# cubesat_board_connector.net
KiCad netlist of a schematic drawn in Altium Designer
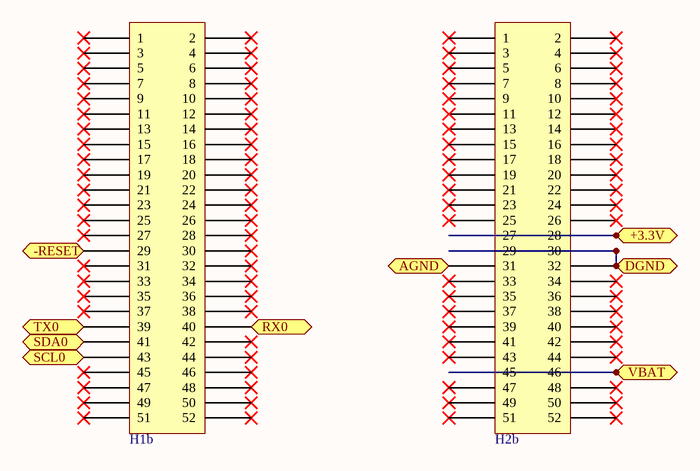
[diagram p0: cubesat board connector.SchDoc]

(export (version "E")
  (design (tool "Eeschema 10.0.6"))
  (components
    (comp (ref "H1b") (value "CSC Header") (libsource (lib "allspace_schem") (part "CubeSat Connector")))
    (comp (ref "H2b") (value "CSC Header") (libsource (lib "allspace_schem") (part "CubeSat Connector")))
  )
  (nets
    (net (code "1") (name "/+3.3V") (class "Default")
      (node (ref "H2b") (pin "27") (pinfunction "27_27") (pintype "passive"))
      (node (ref "H2b") (pin "28") (pinfunction "28_28") (pintype "passive"))
    )
    (net (code "2") (name "/-RESET") (class "Default")
      (node (ref "H1b") (pin "29") (pinfunction "29_29") (pintype "passive"))
    )
    (net (code "3") (name "/AGND") (class "Default")
      (node (ref "H2b") (pin "31") (pinfunction "31_31") (pintype "passive"))
    )
    (net (code "4") (name "/DGND") (class "Default")
      (node (ref "H2b") (pin "29") (pinfunction "29_29") (pintype "passive"))
      (node (ref "H2b") (pin "30") (pinfunction "30_30") (pintype "passive"))
      (node (ref "H2b") (pin "32") (pinfunction "32_32") (pintype "passive"))
    )
    (net (code "5") (name "/RX0") (class "Default")
      (node (ref "H1b") (pin "40") (pinfunction "40_40") (pintype "passive"))
    )
    (net (code "6") (name "/SCL0") (class "Default")
      (node (ref "H1b") (pin "43") (pinfunction "43_43") (pintype "passive"))
    )
    (net (code "7") (name "/SDA0") (class "Default")
      (node (ref "H1b") (pin "41") (pinfunction "41_41") (pintype "passive"))
    )
    (net (code "8") (name "/TX0") (class "Default")
      (node (ref "H1b") (pin "39") (pinfunction "39_39") (pintype "passive"))
    )
    (net (code "9") (name "/VBAT") (class "Default")
      (node (ref "H2b") (pin "45") (pinfunction "45_45") (pintype "passive"))
      (node (ref "H2b") (pin "46") (pinfunction "46_46") (pintype "passive"))
    )
    (net (code "10") (name "unconnected-(H1b-Pad1)") (class "Default")
      (node (ref "H1b") (pin "1") (pinfunction "1_1") (pintype "passive+no_connect"))
    )
    (net (code "11") (name "unconnected-(H1b-Pad2)") (class "Default")
      (node (ref "H1b") (pin "2") (pinfunction "2_2") (pintype "passive+no_connect"))
    )
    (net (code "12") (name "unconnected-(H1b-Pad3)") (class "Default")
      (node (ref "H1b") (pin "3") (pinfunction "3_3") (pintype "passive+no_connect"))
    )
    (net (code "13") (name "unconnected-(H1b-Pad4)") (class "Default")
      (node (ref "H1b") (pin "4") (pinfunction "4_4") (pintype "passive+no_connect"))
    )
    (net (code "14") (name "unconnected-(H1b-Pad5)") (class "Default")
      (node (ref "H1b") (pin "5") (pinfunction "5_5") (pintype "passive+no_connect"))
    )
    (net (code "15") (name "unconnected-(H1b-Pad6)") (class "Default")
      (node (ref "H1b") (pin "6") (pinfunction "6_6") (pintype "passive+no_connect"))
    )
    (net (code "16") (name "unconnected-(H1b-Pad7)") (class "Default")
      (node (ref "H1b") (pin "7") (pinfunction "7_7") (pintype "passive+no_connect"))
    )
    (net (code "17") (name "unconnected-(H1b-Pad8)") (class "Default")
      (node (ref "H1b") (pin "8") (pinfunction "8_8") (pintype "passive+no_connect"))
    )
    (net (code "18") (name "unconnected-(H1b-Pad9)") (class "Default")
      (node (ref "H1b") (pin "9") (pinfunction "9_9") (pintype "passive+no_connect"))
    )
    (net (code "19") (name "unconnected-(H1b-Pad10)") (class "Default")
      (node (ref "H1b") (pin "10") (pinfunction "10_10") (pintype "passive+no_connect"))
    )
    (net (code "20") (name "unconnected-(H1b-Pad11)") (class "Default")
      (node (ref "H1b") (pin "11") (pinfunction "11_11") (pintype "passive+no_connect"))
    )
    (net (code "21") (name "unconnected-(H1b-Pad12)") (class "Default")
      (node (ref "H1b") (pin "12") (pinfunction "12_12") (pintype "passive+no_connect"))
    )
    (net (code "22") (name "unconnected-(H1b-Pad13)") (class "Default")
      (node (ref "H1b") (pin "13") (pinfunction "13_13") (pintype "passive+no_connect"))
    )
    (net (code "23") (name "unconnected-(H1b-Pad14)") (class "Default")
      (node (ref "H1b") (pin "14") (pinfunction "14_14") (pintype "passive+no_connect"))
    )
    (net (code "24") (name "unconnected-(H1b-Pad15)") (class "Default")
      (node (ref "H1b") (pin "15") (pinfunction "15_15") (pintype "passive+no_connect"))
    )
    (net (code "25") (name "unconnected-(H1b-Pad16)") (class "Default")
      (node (ref "H1b") (pin "16") (pinfunction "16_16") (pintype "passive+no_connect"))
    )
    (net (code "26") (name "unconnected-(H1b-Pad17)") (class "Default")
      (node (ref "H1b") (pin "17") (pinfunction "17_17") (pintype "passive+no_connect"))
    )
    (net (code "27") (name "unconnected-(H1b-Pad18)") (class "Default")
      (node (ref "H1b") (pin "18") (pinfunction "18_18") (pintype "passive+no_connect"))
    )
    (net (code "28") (name "unconnected-(H1b-Pad19)") (class "Default")
      (node (ref "H1b") (pin "19") (pinfunction "19_19") (pintype "passive+no_connect"))
    )
    (net (code "29") (name "unconnected-(H1b-Pad20)") (class "Default")
      (node (ref "H1b") (pin "20") (pinfunction "20_20") (pintype "passive+no_connect"))
    )
    (net (code "30") (name "unconnected-(H1b-Pad21)") (class "Default")
      (node (ref "H1b") (pin "21") (pinfunction "21_21") (pintype "passive+no_connect"))
    )
    (net (code "31") (name "unconnected-(H1b-Pad22)") (class "Default")
      (node (ref "H1b") (pin "22") (pinfunction "22_22") (pintype "passive+no_connect"))
    )
    (net (code "32") (name "unconnected-(H1b-Pad23)") (class "Default")
      (node (ref "H1b") (pin "23") (pinfunction "23_23") (pintype "passive+no_connect"))
    )
    (net (code "33") (name "unconnected-(H1b-Pad24)") (class "Default")
      (node (ref "H1b") (pin "24") (pinfunction "24_24") (pintype "passive+no_connect"))
    )
    (net (code "34") (name "unconnected-(H1b-Pad25)") (class "Default")
      (node (ref "H1b") (pin "25") (pinfunction "25_25") (pintype "passive+no_connect"))
    )
    (net (code "35") (name "unconnected-(H1b-Pad26)") (class "Default")
      (node (ref "H1b") (pin "26") (pinfunction "26_26") (pintype "passive+no_connect"))
    )
    (net (code "36") (name "unconnected-(H1b-Pad27)") (class "Default")
      (node (ref "H1b") (pin "27") (pinfunction "27_27") (pintype "passive+no_connect"))
    )
    (net (code "37") (name "unconnected-(H1b-Pad28)") (class "Default")
      (node (ref "H1b") (pin "28") (pinfunction "28_28") (pintype "passive+no_connect"))
    )
    (net (code "38") (name "unconnected-(H1b-Pad30)") (class "Default")
      (node (ref "H1b") (pin "30") (pinfunction "30_30") (pintype "passive+no_connect"))
    )
    (net (code "39") (name "unconnected-(H1b-Pad31)") (class "Default")
      (node (ref "H1b") (pin "31") (pinfunction "31_31") (pintype "passive+no_connect"))
    )
    (net (code "40") (name "unconnected-(H1b-Pad32)") (class "Default")
      (node (ref "H1b") (pin "32") (pinfunction "32_32") (pintype "passive+no_connect"))
    )
    (net (code "41") (name "unconnected-(H1b-Pad33)") (class "Default")
      (node (ref "H1b") (pin "33") (pinfunction "33_33") (pintype "passive+no_connect"))
    )
    (net (code "42") (name "unconnected-(H1b-Pad34)") (class "Default")
      (node (ref "H1b") (pin "34") (pinfunction "34_34") (pintype "passive+no_connect"))
    )
    (net (code "43") (name "unconnected-(H1b-Pad35)") (class "Default")
      (node (ref "H1b") (pin "35") (pinfunction "35_35") (pintype "passive+no_connect"))
    )
    (net (code "44") (name "unconnected-(H1b-Pad36)") (class "Default")
      (node (ref "H1b") (pin "36") (pinfunction "36_36") (pintype "passive+no_connect"))
    )
    (net (code "45") (name "unconnected-(H1b-Pad37)") (class "Default")
      (node (ref "H1b") (pin "37") (pinfunction "37_37") (pintype "passive+no_connect"))
    )
    (net (code "46") (name "unconnected-(H1b-Pad38)") (class "Default")
      (node (ref "H1b") (pin "38") (pinfunction "38_38") (pintype "passive+no_connect"))
    )
    (net (code "47") (name "unconnected-(H1b-Pad42)") (class "Default")
      (node (ref "H1b") (pin "42") (pinfunction "42_42") (pintype "passive+no_connect"))
    )
    (net (code "48") (name "unconnected-(H1b-Pad44)") (class "Default")
      (node (ref "H1b") (pin "44") (pinfunction "44_44") (pintype "passive+no_connect"))
    )
    (net (code "49") (name "unconnected-(H1b-Pad45)") (class "Default")
      (node (ref "H1b") (pin "45") (pinfunction "45_45") (pintype "passive+no_connect"))
    )
    (net (code "50") (name "unconnected-(H1b-Pad46)") (class "Default")
      (node (ref "H1b") (pin "46") (pinfunction "46_46") (pintype "passive+no_connect"))
    )
    (net (code "51") (name "unconnected-(H1b-Pad47)") (class "Default")
      (node (ref "H1b") (pin "47") (pinfunction "47_47") (pintype "passive+no_connect"))
    )
    (net (code "52") (name "unconnected-(H1b-Pad48)") (class "Default")
      (node (ref "H1b") (pin "48") (pinfunction "48_48") (pintype "passive+no_connect"))
    )
    (net (code "53") (name "unconnected-(H1b-Pad49)") (class "Default")
      (node (ref "H1b") (pin "49") (pinfunction "49_49") (pintype "passive+no_connect"))
    )
    (net (code "54") (name "unconnected-(H1b-Pad50)") (class "Default")
      (node (ref "H1b") (pin "50") (pinfunction "50_50") (pintype "passive+no_connect"))
    )
    (net (code "55") (name "unconnected-(H1b-Pad51)") (class "Default")
      (node (ref "H1b") (pin "51") (pinfunction "51_51") (pintype "passive+no_connect"))
    )
    (net (code "56") (name "unconnected-(H1b-Pad52)") (class "Default")
      (node (ref "H1b") (pin "52") (pinfunction "52_52") (pintype "passive+no_connect"))
    )
    (net (code "57") (name "unconnected-(H2b-Pad1)") (class "Default")
      (node (ref "H2b") (pin "1") (pinfunction "1_1") (pintype "passive+no_connect"))
    )
    (net (code "58") (name "unconnected-(H2b-Pad2)") (class "Default")
      (node (ref "H2b") (pin "2") (pinfunction "2_2") (pintype "passive+no_connect"))
    )
    (net (code "59") (name "unconnected-(H2b-Pad3)") (class "Default")
      (node (ref "H2b") (pin "3") (pinfunction "3_3") (pintype "passive+no_connect"))
    )
    (net (code "60") (name "unconnected-(H2b-Pad4)") (class "Default")
      (node (ref "H2b") (pin "4") (pinfunction "4_4") (pintype "passive+no_connect"))
    )
    (net (code "61") (name "unconnected-(H2b-Pad5)") (class "Default")
      (node (ref "H2b") (pin "5") (pinfunction "5_5") (pintype "passive+no_connect"))
    )
    (net (code "62") (name "unconnected-(H2b-Pad6)") (class "Default")
      (node (ref "H2b") (pin "6") (pinfunction "6_6") (pintype "passive+no_connect"))
    )
    (net (code "63") (name "unconnected-(H2b-Pad7)") (class "Default")
      (node (ref "H2b") (pin "7") (pinfunction "7_7") (pintype "passive+no_connect"))
    )
    (net (code "64") (name "unconnected-(H2b-Pad8)") (class "Default")
      (node (ref "H2b") (pin "8") (pinfunction "8_8") (pintype "passive+no_connect"))
    )
    (net (code "65") (name "unconnected-(H2b-Pad9)") (class "Default")
      (node (ref "H2b") (pin "9") (pinfunction "9_9") (pintype "passive+no_connect"))
    )
    (net (code "66") (name "unconnected-(H2b-Pad10)") (class "Default")
      (node (ref "H2b") (pin "10") (pinfunction "10_10") (pintype "passive+no_connect"))
    )
    (net (code "67") (name "unconnected-(H2b-Pad11)") (class "Default")
      (node (ref "H2b") (pin "11") (pinfunction "11_11") (pintype "passive+no_connect"))
    )
    (net (code "68") (name "unconnected-(H2b-Pad12)") (class "Default")
      (node (ref "H2b") (pin "12") (pinfunction "12_12") (pintype "passive+no_connect"))
    )
    (net (code "69") (name "unconnected-(H2b-Pad13)") (class "Default")
      (node (ref "H2b") (pin "13") (pinfunction "13_13") (pintype "passive+no_connect"))
    )
    (net (code "70") (name "unconnected-(H2b-Pad14)") (class "Default")
      (node (ref "H2b") (pin "14") (pinfunction "14_14") (pintype "passive+no_connect"))
    )
    (net (code "71") (name "unconnected-(H2b-Pad15)") (class "Default")
      (node (ref "H2b") (pin "15") (pinfunction "15_15") (pintype "passive+no_connect"))
    )
    (net (code "72") (name "unconnected-(H2b-Pad16)") (class "Default")
      (node (ref "H2b") (pin "16") (pinfunction "16_16") (pintype "passive+no_connect"))
    )
    (net (code "73") (name "unconnected-(H2b-Pad17)") (class "Default")
      (node (ref "H2b") (pin "17") (pinfunction "17_17") (pintype "passive+no_connect"))
    )
    (net (code "74") (name "unconnected-(H2b-Pad18)") (class "Default")
      (node (ref "H2b") (pin "18") (pinfunction "18_18") (pintype "passive+no_connect"))
    )
    (net (code "75") (name "unconnected-(H2b-Pad19)") (class "Default")
      (node (ref "H2b") (pin "19") (pinfunction "19_19") (pintype "passive+no_connect"))
    )
    (net (code "76") (name "unconnected-(H2b-Pad20)") (class "Default")
      (node (ref "H2b") (pin "20") (pinfunction "20_20") (pintype "passive+no_connect"))
    )
    (net (code "77") (name "unconnected-(H2b-Pad21)") (class "Default")
      (node (ref "H2b") (pin "21") (pinfunction "21_21") (pintype "passive+no_connect"))
    )
    (net (code "78") (name "unconnected-(H2b-Pad22)") (class "Default")
      (node (ref "H2b") (pin "22") (pinfunction "22_22") (pintype "passive+no_connect"))
    )
    (net (code "79") (name "unconnected-(H2b-Pad23)") (class "Default")
      (node (ref "H2b") (pin "23") (pinfunction "23_23") (pintype "passive+no_connect"))
    )
    (net (code "80") (name "unconnected-(H2b-Pad24)") (class "Default")
      (node (ref "H2b") (pin "24") (pinfunction "24_24") (pintype "passive+no_connect"))
    )
    (net (code "81") (name "unconnected-(H2b-Pad25)") (class "Default")
      (node (ref "H2b") (pin "25") (pinfunction "25_25") (pintype "passive+no_connect"))
    )
    (net (code "82") (name "unconnected-(H2b-Pad26)") (class "Default")
      (node (ref "H2b") (pin "26") (pinfunction "26_26") (pintype "passive+no_connect"))
    )
    (net (code "83") (name "unconnected-(H2b-Pad33)") (class "Default")
      (node (ref "H2b") (pin "33") (pinfunction "33_33") (pintype "passive+no_connect"))
    )
    (net (code "84") (name "unconnected-(H2b-Pad34)") (class "Default")
      (node (ref "H2b") (pin "34") (pinfunction "34_34") (pintype "passive+no_connect"))
    )
    (net (code "85") (name "unconnected-(H2b-Pad35)") (class "Default")
      (node (ref "H2b") (pin "35") (pinfunction "35_35") (pintype "passive+no_connect"))
    )
    (net (code "86") (name "unconnected-(H2b-Pad36)") (class "Default")
      (node (ref "H2b") (pin "36") (pinfunction "36_36") (pintype "passive+no_connect"))
    )
    (net (code "87") (name "unconnected-(H2b-Pad37)") (class "Default")
      (node (ref "H2b") (pin "37") (pinfunction "37_37") (pintype "passive+no_connect"))
    )
    (net (code "88") (name "unconnected-(H2b-Pad38)") (class "Default")
      (node (ref "H2b") (pin "38") (pinfunction "38_38") (pintype "passive+no_connect"))
    )
    (net (code "89") (name "unconnected-(H2b-Pad39)") (class "Default")
      (node (ref "H2b") (pin "39") (pinfunction "39_39") (pintype "passive+no_connect"))
    )
    (net (code "90") (name "unconnected-(H2b-Pad40)") (class "Default")
      (node (ref "H2b") (pin "40") (pinfunction "40_40") (pintype "passive+no_connect"))
    )
    (net (code "91") (name "unconnected-(H2b-Pad41)") (class "Default")
      (node (ref "H2b") (pin "41") (pinfunction "41_41") (pintype "passive+no_connect"))
    )
    (net (code "92") (name "unconnected-(H2b-Pad42)") (class "Default")
      (node (ref "H2b") (pin "42") (pinfunction "42_42") (pintype "passive+no_connect"))
    )
    (net (code "93") (name "unconnected-(H2b-Pad43)") (class "Default")
      (node (ref "H2b") (pin "43") (pinfunction "43_43") (pintype "passive+no_connect"))
    )
    (net (code "94") (name "unconnected-(H2b-Pad44)") (class "Default")
      (node (ref "H2b") (pin "44") (pinfunction "44_44") (pintype "passive+no_connect"))
    )
    (net (code "95") (name "unconnected-(H2b-Pad47)") (class "Default")
      (node (ref "H2b") (pin "47") (pinfunction "47_47") (pintype "passive+no_connect"))
    )
    (net (code "96") (name "unconnected-(H2b-Pad48)") (class "Default")
      (node (ref "H2b") (pin "48") (pinfunction "48_48") (pintype "passive+no_connect"))
    )
    (net (code "97") (name "unconnected-(H2b-Pad49)") (class "Default")
      (node (ref "H2b") (pin "49") (pinfunction "49_49") (pintype "passive+no_connect"))
    )
    (net (code "98") (name "unconnected-(H2b-Pad50)") (class "Default")
      (node (ref "H2b") (pin "50") (pinfunction "50_50") (pintype "passive+no_connect"))
    )
    (net (code "99") (name "unconnected-(H2b-Pad51)") (class "Default")
      (node (ref "H2b") (pin "51") (pinfunction "51_51") (pintype "passive+no_connect"))
    )
    (net (code "100") (name "unconnected-(H2b-Pad52)") (class "Default")
      (node (ref "H2b") (pin "52") (pinfunction "52_52") (pintype "passive+no_connect"))
    )
  )
)
